# RoboKit.net
KiCad netlist of a schematic drawn in EAGLE
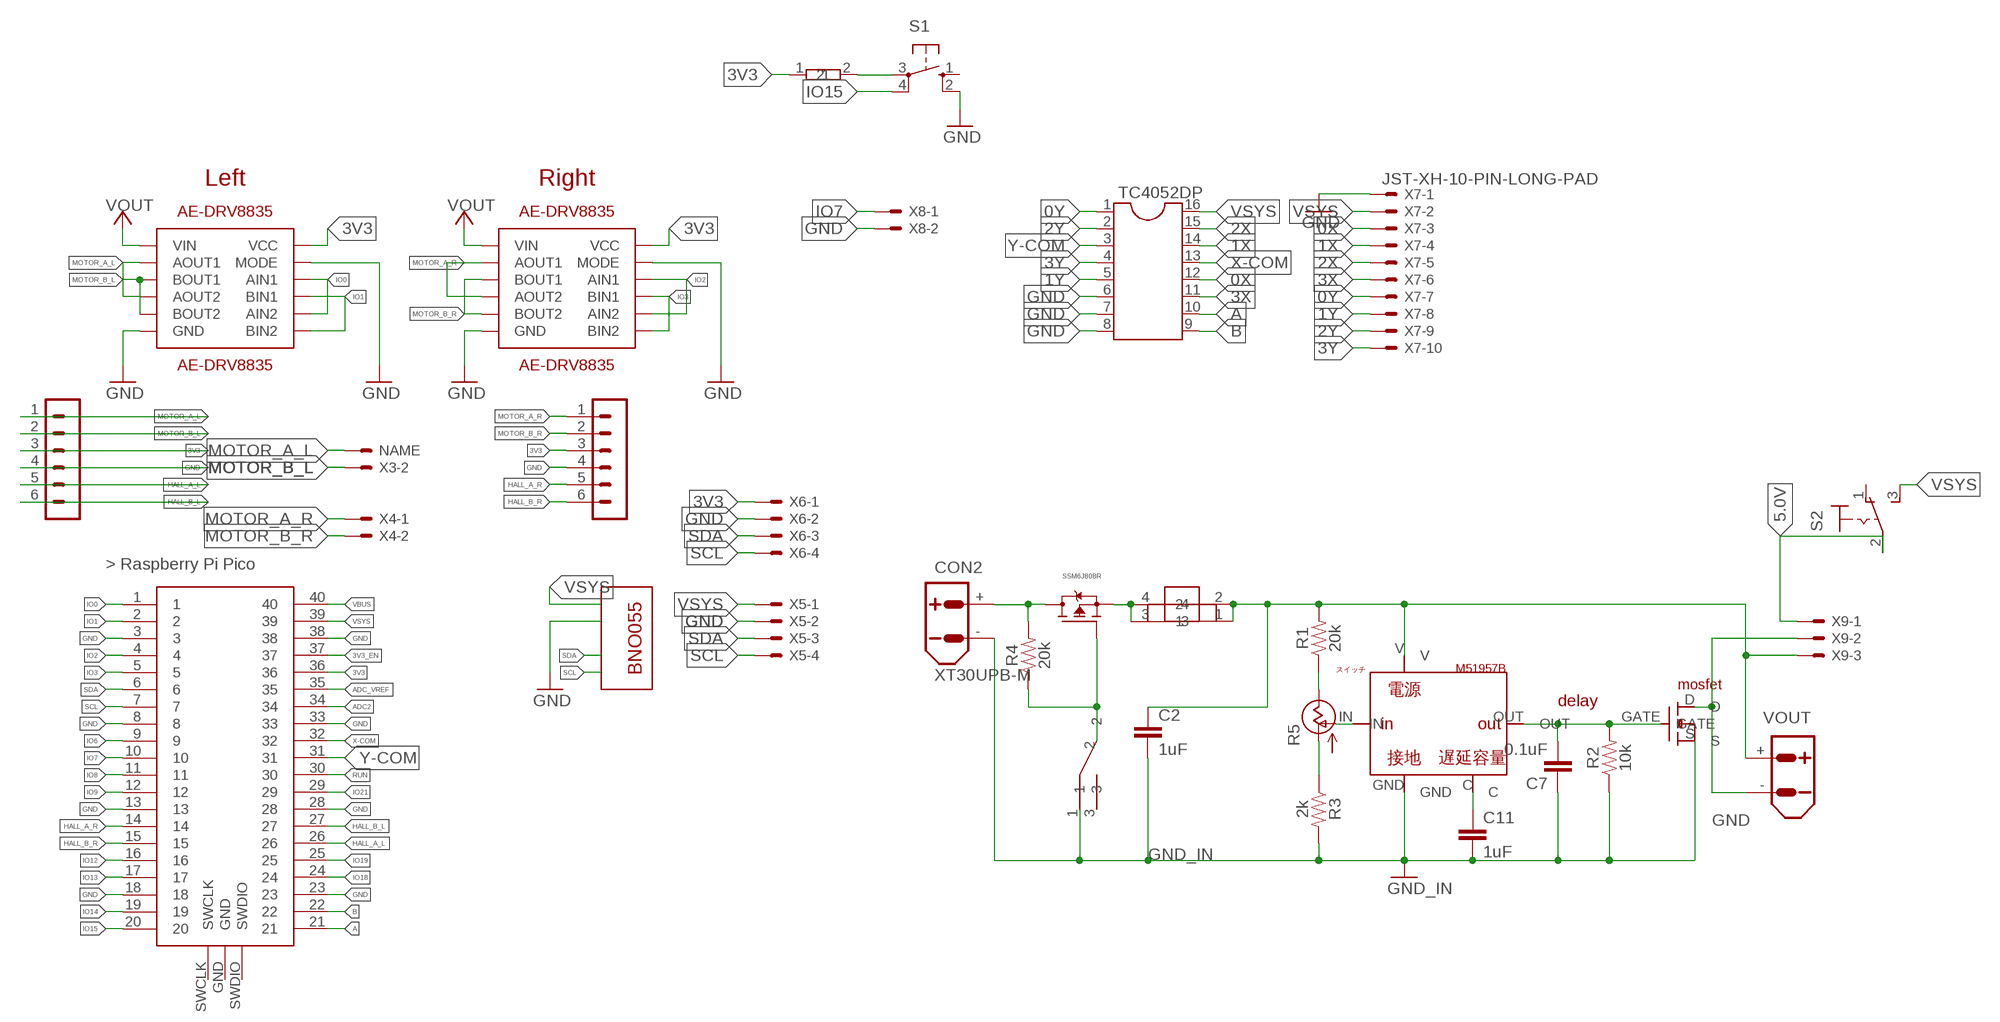
[diagram p0: schematic, sheet 1]

(export (version "E")
  (design (tool "Eeschema 10.0.6"))
  (components
    (comp (ref "C2")
      (value "1uF")
      (footprint "eagle-import:C0603")
      (libsource (lib "eagle-import") (part "C-EUC0603"))
    )
    (comp (ref "C7")
      (value "0.1uF")
      (footprint "eagle-import:0603")
      (libsource (lib "eagle-import") (part "4.7UF0603"))
    )
    (comp (ref "C11")
      (value "1uF")
      (footprint "eagle-import:C0603")
      (libsource (lib "eagle-import") (part "C-EUC0603"))
    )
    (comp (ref "CON1")
      (value "XT30UPB-M")
      (footprint "eagle-import:XT30UPB-M")
      (libsource (lib "eagle-import") (part "XT30UPB-M"))
    )
    (comp (ref "CON2")
      (value "XT30UPB-M")
      (footprint "eagle-import:XT30UPB-M")
      (libsource (lib "eagle-import") (part "XT30UPB-M"))
    )
    (comp (ref "CONNECTOR1")
      (value "RESISTER")
      (footprint "eagle-import:RESISTER_SOCKET")
      (libsource (lib "eagle-import") (part "RESISTER"))
    )
    (comp (ref "P1")
      (value "B6B-PH-K")
      (footprint "eagle-import:B6B-PH-K")
      (libsource (lib "eagle-import") (part "B6B-PH-K"))
    )
    (comp (ref "P2")
      (value "B6B-PH-K")
      (footprint "eagle-import:B6B-PH-K")
      (libsource (lib "eagle-import") (part "B6B-PH-K"))
    )
    (comp (ref "R1")
      (value "20k")
      (footprint "eagle-import:0603")
      (libsource (lib "eagle-import") (part "10KOHM-0603-1/10W-1%"))
    )
    (comp (ref "R2")
      (value "10k")
      (footprint "eagle-import:0603")
      (libsource (lib "eagle-import") (part "1KOHM-0603-1/10W-1%"))
    )
    (comp (ref "R3")
      (value "2k")
      (footprint "eagle-import:0603")
      (libsource (lib "eagle-import") (part "1KOHM-0603-1/10W-1%"))
    )
    (comp (ref "R4")
      (value "20k")
      (footprint "eagle-import:0603")
      (libsource (lib "eagle-import") (part "10KOHM-0603-1/10W-1%"))
    )
    (comp (ref "R5")
      (value "1k")
      (footprint "eagle-import:S64W")
      (libsource (lib "eagle-import") (part "POTTRS64W"))
    )
    (comp (ref "S1")
      (value "10-XX")
      (footprint "eagle-import:B3F-10XX")
      (fields (field (name "MPN") "B3F-1000"))
      (libsource (lib "eagle-import") (part "10-XX"))
    )
    (comp (ref "S2")
      (value "320-916")
      (footprint "eagle-import:320-916")
      (libsource (lib "eagle-import") (part "320-916"))
    )
    (comp (ref "TC4052DP")
      (value "DIL16")
      (footprint "eagle-import:DIL16")
      (libsource (lib "eagle-import") (part "DIL16"))
    )
    (comp (ref "U$1")
      (value "RASPBERRY-PI-PICO_TH")
      (footprint "eagle-import:FT_RASPBERRY-PI-PICO_TH")
      (libsource (lib "eagle-import") (part "RASPBERRY-PI-PICO_TH"))
    )
    (comp (ref "U$2")
      (value "AE-DRV8835")
      (footprint "eagle-import:AE-DRV8835")
      (libsource (lib "eagle-import") (part "AE-DRV8835"))
    )
    (comp (ref "U$3")
      (value "AE-DRV8835")
      (footprint "eagle-import:AE-DRV8835")
      (libsource (lib "eagle-import") (part "AE-DRV8835"))
    )
    (comp (ref "U$4")
      (value "AE-BNO055-BO")
      (footprint "eagle-import:AE-BNO055-BO")
      (libsource (lib "eagle-import") (part "AE-BNO055-BO"))
    )
    (comp (ref "U$5")
      (value "M51957")
      (footprint "eagle-import:SOP-8")
      (libsource (lib "eagle-import") (part "M51957"))
    )
    (comp (ref "U$6")
      (value "BSC093N04LSGATMA1")
      (footprint "eagle-import:MOSFET_BSC093N04LSGATMA1")
      (libsource (lib "eagle-import") (part "BSC093N04LSGATMA1"))
    )
    (comp (ref "U$7")
      (value "FUSE")
      (footprint "eagle-import:FUSE")
      (libsource (lib "eagle-import") (part "FUSE"))
    )
    (comp (ref "U$9") (value "SW") (footprint "eagle-import:SW") (libsource (lib "eagle-import") (part "SW")))
    (comp (ref "U1")
      (value "SSM6J808R")
      (footprint "eagle-import:SSM6J808R")
      (fields (field (name "MANUFACTURER") "Toshiba"))
      (libsource (lib "eagle-import") (part "SSM6J808R"))
    )
    (comp (ref "X3")
      (value "JST-XH-02-PIN-LONG-PAD")
      (footprint "eagle-import:JST-XH-02-PACKAGE-LONG-PAD")
      (libsource (lib "eagle-import") (part "JST-XH-02-PIN-LONG-PAD"))
    )
    (comp (ref "X4")
      (value "JST-XH-02-PIN-LONG-PAD")
      (footprint "eagle-import:JST-XH-02-PACKAGE-LONG-PAD")
      (libsource (lib "eagle-import") (part "JST-XH-02-PIN-LONG-PAD"))
    )
    (comp (ref "X5")
      (value "JST-XH-04-PIN-LONG-PAD")
      (footprint "eagle-import:JST-XH-04-PACKAGE-LONG-PAD")
      (libsource (lib "eagle-import") (part "JST-XH-04-PIN-LONG-PAD"))
    )
    (comp (ref "X6")
      (value "JST-XH-04-PIN-LONG-PAD")
      (footprint "eagle-import:JST-XH-04-PACKAGE-LONG-PAD")
      (libsource (lib "eagle-import") (part "JST-XH-04-PIN-LONG-PAD"))
    )
    (comp (ref "X7")
      (value "JST-XH-10-PIN-LONG-PAD")
      (footprint "eagle-import:JST-XH-10-PACKAGE-LONG-PAD")
      (libsource (lib "eagle-import") (part "JST-XH-10-PIN-LONG-PAD"))
    )
    (comp (ref "X8")
      (value "JST-XH-02-PIN-LONG-PAD")
      (footprint "eagle-import:JST-XH-02-PACKAGE-LONG-PAD")
      (libsource (lib "eagle-import") (part "JST-XH-02-PIN-LONG-PAD"))
    )
    (comp (ref "X9")
      (value "JST-XH-03-PIN-LONG-PAD")
      (footprint "eagle-import:JST-XH-03-PACKAGE-LONG-PAD")
      (libsource (lib "eagle-import") (part "JST-XH-03-PIN-LONG-PAD"))
    )
  )
  (nets
    (net (code "1") (name "0X") (class "Default")
      (node (ref "TC4052DP") (pin "12") (pinfunction "12_12") (pintype "passive"))
      (node (ref "X7") (pin "3") (pinfunction "S_3") (pintype "passive"))
    )
    (net (code "2") (name "0Y") (class "Default")
      (node (ref "TC4052DP") (pin "1") (pinfunction "1_1") (pintype "passive"))
      (node (ref "X7") (pin "7") (pinfunction "S_7") (pintype "passive"))
    )
    (net (code "3") (name "1X") (class "Default")
      (node (ref "TC4052DP") (pin "14") (pinfunction "14_14") (pintype "passive"))
      (node (ref "X7") (pin "4") (pinfunction "S_4") (pintype "passive"))
    )
    (net (code "4") (name "1Y") (class "Default")
      (node (ref "TC4052DP") (pin "5") (pinfunction "5_5") (pintype "passive"))
      (node (ref "X7") (pin "8") (pinfunction "S_8") (pintype "passive"))
    )
    (net (code "5") (name "2X") (class "Default")
      (node (ref "TC4052DP") (pin "15") (pinfunction "15_15") (pintype "passive"))
      (node (ref "X7") (pin "5") (pinfunction "S_5") (pintype "passive"))
    )
    (net (code "6") (name "2Y") (class "Default")
      (node (ref "TC4052DP") (pin "2") (pinfunction "2_2") (pintype "passive"))
      (node (ref "X7") (pin "9") (pinfunction "S_9") (pintype "passive"))
    )
    (net (code "7") (name "3V3") (class "Default")
      (node (ref "CONNECTOR1") (pin "1") (pinfunction "1_1") (pintype "bidirectional"))
      (node (ref "P1") (pin "3") (pinfunction "3_3") (pintype "passive"))
      (node (ref "P2") (pin "3") (pinfunction "3_3") (pintype "passive"))
      (node (ref "U$1") (pin "36") (pinfunction "36_36") (pintype "bidirectional"))
      (node (ref "U$2") (pin "VCC") (pinfunction "VCC_VCC") (pintype "input"))
      (node (ref "U$3") (pin "VCC") (pinfunction "VCC_VCC") (pintype "input"))
      (node (ref "X6") (pin "1") (pinfunction "S_1") (pintype "passive"))
    )
    (net (code "8") (name "3V3_EN") (class "Default")
      (node (ref "U$1") (pin "37") (pinfunction "37_37") (pintype "bidirectional"))
    )
    (net (code "9") (name "3X") (class "Default")
      (node (ref "TC4052DP") (pin "11") (pinfunction "11_11") (pintype "passive"))
      (node (ref "X7") (pin "6") (pinfunction "S_6") (pintype "passive"))
    )
    (net (code "10") (name "3Y") (class "Default")
      (node (ref "TC4052DP") (pin "4") (pinfunction "4_4") (pintype "passive"))
      (node (ref "X7") (pin "10") (pinfunction "S_10") (pintype "passive"))
    )
    (net (code "11") (name "5.0V") (class "Default")
      (node (ref "S2") (pin "2") (pinfunction "P_2") (pintype "passive"))
      (node (ref "X9") (pin "1") (pinfunction "S_1") (pintype "passive"))
    )
    (net (code "12") (name "A") (class "Default")
      (node (ref "TC4052DP") (pin "10") (pinfunction "10_10") (pintype "passive"))
      (node (ref "U$1") (pin "21") (pinfunction "21_21") (pintype "bidirectional"))
    )
    (net (code "13") (name "ADC2") (class "Default")
      (node (ref "U$1") (pin "34") (pinfunction "34_34") (pintype "bidirectional"))
    )
    (net (code "14") (name "ADC_VREF") (class "Default")
      (node (ref "U$1") (pin "35") (pinfunction "35_35") (pintype "bidirectional"))
    )
    (net (code "15") (name "B") (class "Default")
      (node (ref "TC4052DP") (pin "9") (pinfunction "9_9") (pintype "passive"))
      (node (ref "U$1") (pin "22") (pinfunction "22_22") (pintype "bidirectional"))
    )
    (net (code "16") (name "GND") (class "Default")
      (node (ref "CON1") (pin "-") (pinfunction "-_-") (pintype "power_in"))
      (node (ref "P1") (pin "4") (pinfunction "4_4") (pintype "passive"))
      (node (ref "P2") (pin "4") (pinfunction "4_4") (pintype "passive"))
      (node (ref "S1") (pin "2") (pinfunction "S1_2") (pintype "passive"))
      (node (ref "TC4052DP") (pin "6") (pinfunction "6_6") (pintype "passive"))
      (node (ref "TC4052DP") (pin "7") (pinfunction "7_7") (pintype "passive"))
      (node (ref "TC4052DP") (pin "8") (pinfunction "8_8") (pintype "passive"))
      (node (ref "U$1") (pin "13") (pinfunction "13_13") (pintype "bidirectional"))
      (node (ref "U$1") (pin "18") (pinfunction "18_18") (pintype "bidirectional"))
      (node (ref "U$1") (pin "23") (pinfunction "23_23") (pintype "bidirectional"))
      (node (ref "U$1") (pin "28") (pinfunction "28_28") (pintype "bidirectional"))
      (node (ref "U$1") (pin "3") (pinfunction "3_3") (pintype "bidirectional"))
      (node (ref "U$1") (pin "33") (pinfunction "33_33") (pintype "bidirectional"))
      (node (ref "U$1") (pin "38") (pinfunction "38_38") (pintype "bidirectional"))
      (node (ref "U$1") (pin "8") (pinfunction "8_8") (pintype "bidirectional"))
      (node (ref "U$2") (pin "GND") (pinfunction "GND_GND") (pintype "input"))
      (node (ref "U$2") (pin "MODE") (pinfunction "MODE_MODE") (pintype "input"))
      (node (ref "U$3") (pin "GND") (pinfunction "GND_GND") (pintype "input"))
      (node (ref "U$3") (pin "MODE") (pinfunction "MODE_MODE") (pintype "input"))
      (node (ref "U$4") (pin "GND") (pinfunction "GND_GND") (pintype "bidirectional"))
      (node (ref "U$6") (pin "D") (pinfunction "D_D") (pintype "bidirectional"))
      (node (ref "X5") (pin "2") (pinfunction "S_2") (pintype "passive"))
      (node (ref "X6") (pin "2") (pinfunction "S_2") (pintype "passive"))
      (node (ref "X7") (pin "1") (pinfunction "S_1") (pintype "passive"))
      (node (ref "X8") (pin "2") (pinfunction "S_2") (pintype "passive"))
      (node (ref "X9") (pin "2") (pinfunction "S_2") (pintype "passive"))
    )
    (net (code "17") (name "GND_IN") (class "Default")
      (node (ref "C11") (pin "2") (pinfunction "2_2") (pintype "passive"))
      (node (ref "C2") (pin "2") (pinfunction "2_2") (pintype "passive"))
      (node (ref "C7") (pin "1") (pinfunction "1_1") (pintype "passive"))
      (node (ref "CON2") (pin "-") (pinfunction "-_-") (pintype "power_in"))
      (node (ref "R2") (pin "1") (pinfunction "1_1") (pintype "passive"))
      (node (ref "R3") (pin "2") (pinfunction "2_2") (pintype "passive"))
      (node (ref "U$5") (pin "GND") (pinfunction "GND_GND") (pintype "bidirectional"))
      (node (ref "U$6") (pin "S") (pinfunction "S_S") (pintype "bidirectional"))
      (node (ref "U$9") (pin "1") (pinfunction "1_1") (pintype "bidirectional"))
    )
    (net (code "18") (name "HALL_A_L") (class "Default")
      (node (ref "P2") (pin "5") (pinfunction "5_5") (pintype "passive"))
      (node (ref "U$1") (pin "26") (pinfunction "26_26") (pintype "bidirectional"))
    )
    (net (code "19") (name "HALL_A_R") (class "Default")
      (node (ref "P1") (pin "5") (pinfunction "5_5") (pintype "passive"))
      (node (ref "U$1") (pin "14") (pinfunction "14_14") (pintype "bidirectional"))
    )
    (net (code "20") (name "HALL_B_L") (class "Default")
      (node (ref "P2") (pin "6") (pinfunction "6_6") (pintype "passive"))
      (node (ref "U$1") (pin "27") (pinfunction "27_27") (pintype "bidirectional"))
    )
    (net (code "21") (name "HALL_B_R") (class "Default")
      (node (ref "P1") (pin "6") (pinfunction "6_6") (pintype "passive"))
      (node (ref "U$1") (pin "15") (pinfunction "15_15") (pintype "bidirectional"))
    )
    (net (code "22") (name "IO0") (class "Default")
      (node (ref "U$1") (pin "1") (pinfunction "1_1") (pintype "bidirectional"))
      (node (ref "U$2") (pin "INA1") (pinfunction "AIN1_INA1") (pintype "input"))
      (node (ref "U$2") (pin "INA2") (pinfunction "AIN2_INA2") (pintype "input"))
    )
    (net (code "23") (name "IO1") (class "Default")
      (node (ref "U$1") (pin "2") (pinfunction "2_2") (pintype "bidirectional"))
      (node (ref "U$2") (pin "INB1") (pinfunction "BIN1_INB1") (pintype "input"))
      (node (ref "U$2") (pin "INB2") (pinfunction "BIN2_INB2") (pintype "input"))
    )
    (net (code "24") (name "IO2") (class "Default")
      (node (ref "U$1") (pin "4") (pinfunction "4_4") (pintype "bidirectional"))
      (node (ref "U$3") (pin "INA1") (pinfunction "AIN1_INA1") (pintype "input"))
      (node (ref "U$3") (pin "INA2") (pinfunction "AIN2_INA2") (pintype "input"))
    )
    (net (code "25") (name "IO3") (class "Default")
      (node (ref "U$1") (pin "5") (pinfunction "5_5") (pintype "bidirectional"))
      (node (ref "U$3") (pin "INB1") (pinfunction "BIN1_INB1") (pintype "input"))
      (node (ref "U$3") (pin "INB2") (pinfunction "BIN2_INB2") (pintype "input"))
    )
    (net (code "26") (name "IO6") (class "Default")
      (node (ref "U$1") (pin "9") (pinfunction "9_9") (pintype "bidirectional"))
    )
    (net (code "27") (name "IO7") (class "Default")
      (node (ref "U$1") (pin "10") (pinfunction "10_10") (pintype "bidirectional"))
      (node (ref "X8") (pin "1") (pinfunction "S_1") (pintype "passive"))
    )
    (net (code "28") (name "IO8") (class "Default")
      (node (ref "U$1") (pin "11") (pinfunction "11_11") (pintype "bidirectional"))
    )
    (net (code "29") (name "IO9") (class "Default")
      (node (ref "U$1") (pin "12") (pinfunction "12_12") (pintype "bidirectional"))
    )
    (net (code "30") (name "IO12") (class "Default")
      (node (ref "U$1") (pin "16") (pinfunction "16_16") (pintype "bidirectional"))
    )
    (net (code "31") (name "IO13") (class "Default")
      (node (ref "U$1") (pin "17") (pinfunction "17_17") (pintype "bidirectional"))
    )
    (net (code "32") (name "IO14") (class "Default")
      (node (ref "U$1") (pin "19") (pinfunction "19_19") (pintype "bidirectional"))
    )
    (net (code "33") (name "IO15") (class "Default")
      (node (ref "S1") (pin "4") (pinfunction "P1_4") (pintype "passive"))
      (node (ref "U$1") (pin "20") (pinfunction "20_20") (pintype "bidirectional"))
    )
    (net (code "34") (name "IO18") (class "Default")
      (node (ref "U$1") (pin "24") (pinfunction "24_24") (pintype "bidirectional"))
    )
    (net (code "35") (name "IO19") (class "Default")
      (node (ref "U$1") (pin "25") (pinfunction "25_25") (pintype "bidirectional"))
    )
    (net (code "36") (name "IO21") (class "Default")
      (node (ref "U$1") (pin "29") (pinfunction "29_29") (pintype "bidirectional"))
    )
    (net (code "37") (name "MOTOR_A_L") (class "Default")
      (node (ref "P2") (pin "1") (pinfunction "1_1") (pintype "passive"))
      (node (ref "U$2") (pin "AOUT1") (pinfunction "AOUT1_AOUT1") (pintype "input"))
      (node (ref "U$2") (pin "AOUT2") (pinfunction "AOUT2_AOUT2") (pintype "input"))
      (node (ref "X3") (pin "1") (pinfunction "S_1") (pintype "passive"))
    )
    (net (code "38") (name "MOTOR_A_R") (class "Default")
      (node (ref "P1") (pin "1") (pinfunction "1_1") (pintype "passive"))
      (node (ref "U$3") (pin "AOUT1") (pinfunction "AOUT1_AOUT1") (pintype "input"))
      (node (ref "U$3") (pin "AOUT2") (pinfunction "AOUT2_AOUT2") (pintype "input"))
      (node (ref "X4") (pin "1") (pinfunction "S_1") (pintype "passive"))
    )
    (net (code "39") (name "MOTOR_B_L") (class "Default")
      (node (ref "P2") (pin "2") (pinfunction "2_2") (pintype "passive"))
      (node (ref "U$2") (pin "BOUT1") (pinfunction "BOUT1_BOUT1") (pintype "input"))
      (node (ref "U$2") (pin "BOUT2") (pinfunction "BOUT2_BOUT2") (pintype "input"))
      (node (ref "X3") (pin "2") (pinfunction "S_2") (pintype "passive"))
    )
    (net (code "40") (name "MOTOR_B_R") (class "Default")
      (node (ref "P1") (pin "2") (pinfunction "2_2") (pintype "passive"))
      (node (ref "U$3") (pin "BOUT1") (pinfunction "BOUT1_BOUT1") (pintype "input"))
      (node (ref "U$3") (pin "BOUT2") (pinfunction "BOUT2_BOUT2") (pintype "input"))
      (node (ref "X4") (pin "2") (pinfunction "S_2") (pintype "passive"))
    )
    (net (code "41") (name "Net-(C7-Pad2)") (class "Default")
      (node (ref "C7") (pin "2") (pinfunction "2_2") (pintype "passive"))
      (node (ref "R2") (pin "2") (pinfunction "2_2") (pintype "passive"))
      (node (ref "U$5") (pin "OUT") (pinfunction "OUT_OUT") (pintype "bidirectional"))
      (node (ref "U$6") (pin "GATE") (pinfunction "GATE_GATE") (pintype "bidirectional"))
    )
    (net (code "42") (name "Net-(C11-Pad1)") (class "Default")
      (node (ref "C11") (pin "1") (pinfunction "1_1") (pintype "passive"))
      (node (ref "U$5") (pin "C") (pinfunction "C_C") (pintype "bidirectional"))
    )
    (net (code "43") (name "Net-(CON2-Pad+)") (class "Default")
      (node (ref "CON2") (pin "+") (pinfunction "+_+") (pintype "power_in"))
      (node (ref "R4") (pin "2") (pinfunction "2_2") (pintype "passive"))
      (node (ref "U1") (pin "D") (pinfunction "D_D") (pintype "passive"))
    )
    (net (code "44") (name "Net-(R4-Pad1)") (class "Default")
      (node (ref "R4") (pin "1") (pinfunction "1_1") (pintype "passive"))
      (node (ref "U$9") (pin "2") (pinfunction "2_2") (pintype "bidirectional"))
      (node (ref "U1") (pin "G") (pinfunction "G_G") (pintype "passive"))
    )
    (net (code "45") (name "Net-(R5-OUT)") (class "Default")
      (node (ref "R5") (pin "S") (pinfunction "OUT_S") (pintype "passive"))
      (node (ref "U$5") (pin "IN") (pinfunction "IN_IN") (pintype "bidirectional"))
    )
    (net (code "46") (name "Net-(R5-VDD)") (class "Default")
      (node (ref "R3") (pin "1") (pinfunction "1_1") (pintype "passive"))
      (node (ref "R5") (pin "A") (pinfunction "VDD_A") (pintype "passive"))
    )
    (net (code "47") (name "Net-(R5-VSS)") (class "Default")
      (node (ref "R1") (pin "1") (pinfunction "1_1") (pintype "passive"))
      (node (ref "R5") (pin "E") (pinfunction "VSS_E") (pintype "passive"))
    )
    (net (code "48") (name "Net-(S1-P)") (class "Default")
      (node (ref "CONNECTOR1") (pin "2") (pinfunction "2_2") (pintype "bidirectional"))
      (node (ref "S1") (pin "3") (pinfunction "P_3") (pintype "passive"))
    )
    (net (code "49") (name "Net-(U$7-Pad3)") (class "Default")
      (node (ref "U$7") (pin "3") (pinfunction "3_3") (pintype "bidirectional"))
      (node (ref "U$7") (pin "4") (pinfunction "4_4") (pintype "bidirectional"))
      (node (ref "U1") (pin "S") (pinfunction "S_S") (pintype "passive"))
    )
    (net (code "50") (name "RUN") (class "Default")
      (node (ref "U$1") (pin "30") (pinfunction "30_30") (pintype "bidirectional"))
    )
    (net (code "51") (name "SCL") (class "Default")
      (node (ref "U$1") (pin "7") (pinfunction "7_7") (pintype "bidirectional"))
      (node (ref "U$4") (pin "SCL") (pinfunction "SCL_SCL") (pintype "bidirectional"))
      (node (ref "X5") (pin "4") (pinfunction "S_4") (pintype "passive"))
      (node (ref "X6") (pin "4") (pinfunction "S_4") (pintype "passive"))
    )
    (net (code "52") (name "SDA") (class "Default")
      (node (ref "U$1") (pin "6") (pinfunction "6_6") (pintype "bidirectional"))
      (node (ref "U$4") (pin "SDA") (pinfunction "SDA_SDA") (pintype "bidirectional"))
      (node (ref "X5") (pin "3") (pinfunction "S_3") (pintype "passive"))
      (node (ref "X6") (pin "3") (pinfunction "S_3") (pintype "passive"))
    )
    (net (code "53") (name "VBUS") (class "Default")
      (node (ref "U$1") (pin "40") (pinfunction "40_40") (pintype "bidirectional"))
    )
    (net (code "54") (name "VOUT") (class "Default")
      (node (ref "C2") (pin "1") (pinfunction "1_1") (pintype "passive"))
      (node (ref "CON1") (pin "+") (pinfunction "+_+") (pintype "power_in"))
      (node (ref "R1") (pin "2") (pinfunction "2_2") (pintype "passive"))
      (node (ref "U$2") (pin "VIN") (pinfunction "VIN_VIN") (pintype "input"))
      (node (ref "U$3") (pin "VIN") (pinfunction "VIN_VIN") (pintype "input"))
      (node (ref "U$5") (pin "V") (pinfunction "V_V") (pintype "bidirectional"))
      (node (ref "U$7") (pin "1") (pinfunction "1_1") (pintype "bidirectional"))
      (node (ref "U$7") (pin "2") (pinfunction "2_2") (pintype "bidirectional"))
      (node (ref "X9") (pin "3") (pinfunction "S_3") (pintype "passive"))
    )
    (net (code "55") (name "VSYS") (class "Default")
      (node (ref "S2") (pin "3") (pinfunction "S_3") (pintype "passive"))
      (node (ref "TC4052DP") (pin "16") (pinfunction "16_16") (pintype "passive"))
      (node (ref "U$1") (pin "39") (pinfunction "39_39") (pintype "bidirectional"))
      (node (ref "U$4") (pin "VIN") (pinfunction "VIN_VIN") (pintype "bidirectional"))
      (node (ref "X5") (pin "1") (pinfunction "S_1") (pintype "passive"))
      (node (ref "X7") (pin "2") (pinfunction "S_2") (pintype "passive"))
    )
    (net (code "56") (name "X-COM") (class "Default")
      (node (ref "TC4052DP") (pin "13") (pinfunction "13_13") (pintype "passive"))
      (node (ref "U$1") (pin "32") (pinfunction "32_32") (pintype "bidirectional"))
    )
    (net (code "57") (name "Y-COM") (class "Default")
      (node (ref "TC4052DP") (pin "3") (pinfunction "3_3") (pintype "passive"))
      (node (ref "U$1") (pin "31") (pinfunction "31_31") (pintype "bidirectional"))
    )
    (net (code "58") (name "unconnected-(S1-S-Pad1)") (class "Default")
      (node (ref "S1") (pin "1") (pinfunction "S_1") (pintype "passive"))
    )
    (net (code "59") (name "unconnected-(S2-O-Pad1)") (class "Default")
      (node (ref "S2") (pin "1") (pinfunction "O_1") (pintype "passive"))
    )
    (net (code "60") (name "unconnected-(U$1-PadGND)") (class "Default")
      (node (ref "U$1") (pin "GND") (pinfunction "GND_GND") (pintype "bidirectional"))
    )
    (net (code "61") (name "unconnected-(U$1-PadSWCLK)") (class "Default")
      (node (ref "U$1") (pin "SWCLK") (pinfunction "SWCLK_SWCLK") (pintype "bidirectional"))
    )
    (net (code "62") (name "unconnected-(U$1-PadSWDIO)") (class "Default")
      (node (ref "U$1") (pin "SWDIO") (pinfunction "SWDIO_SWDIO") (pintype "bidirectional"))
    )
    (net (code "63") (name "unconnected-(U$9-Pad3)") (class "Default")
      (node (ref "U$9") (pin "3") (pinfunction "3_3") (pintype "bidirectional"))
    )
  )
)
